# B293B_PSU.net
KiCad netlist of a schematic drawn in Altium Designer
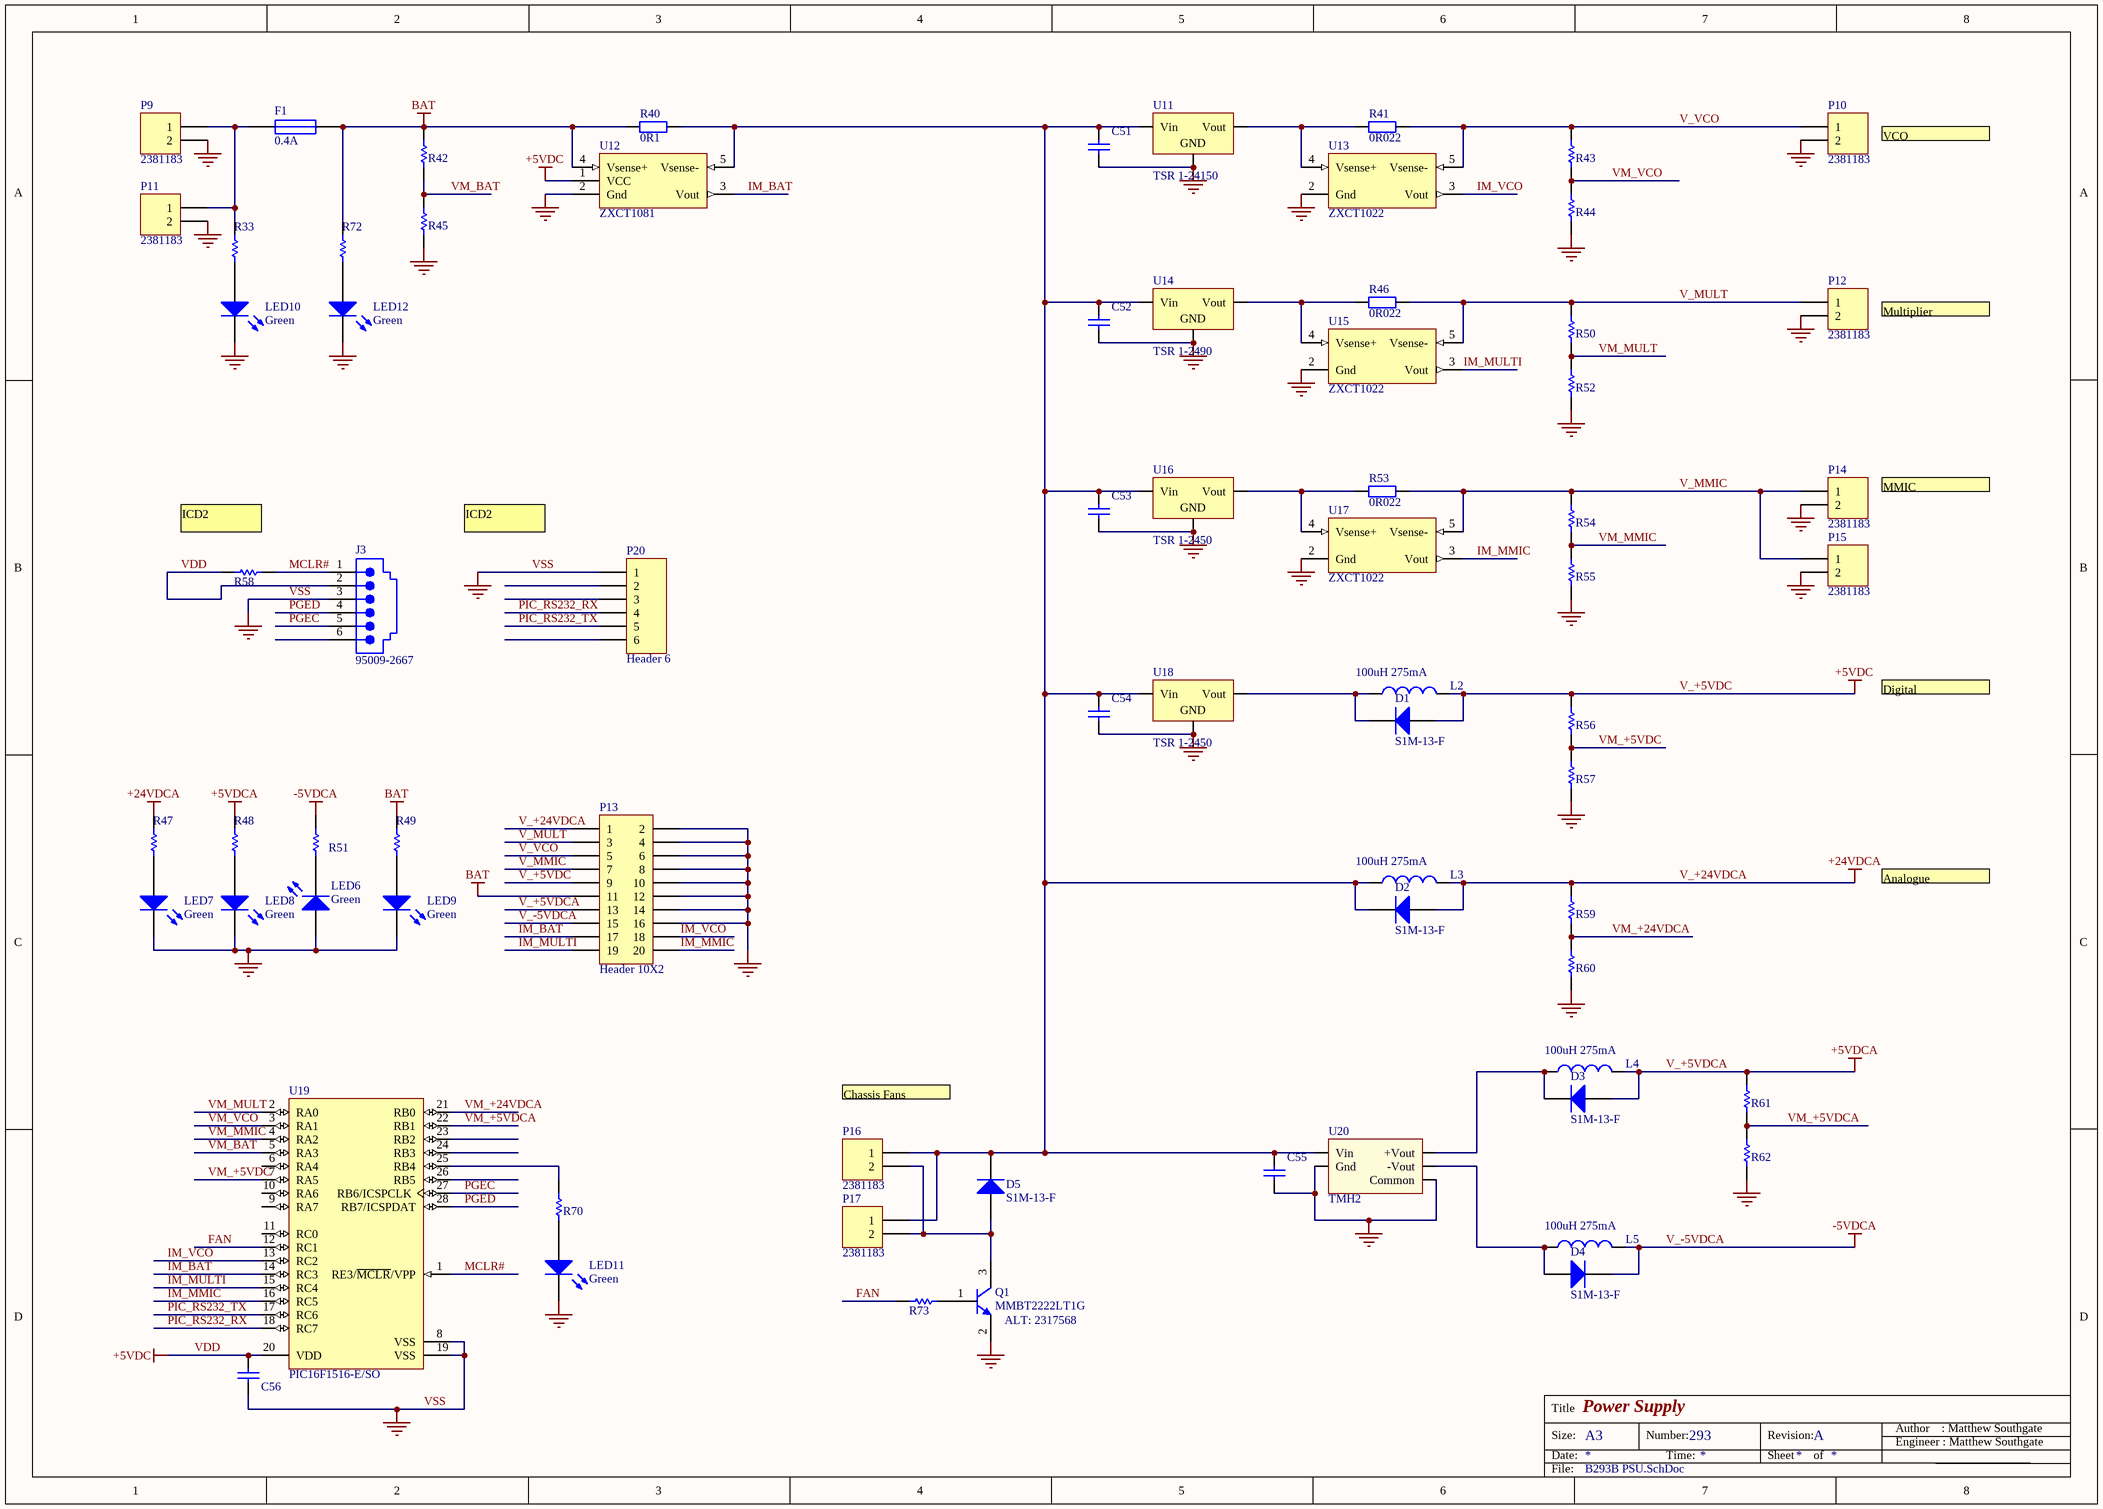
[diagram p0: B293B PSU.SchDoc]

(export (version "E")
  (design (tool "Eeschema 10.0.6"))
  (components
    (comp (ref "C51")
      (value "CAP 10uF 25V 0805(2012)")
      (footprint "CAPC0805(2012)145_N")
      (description "CAP 10uF 25V ±20% 0805 (2012 Metric) Thickness 1.45mm SMD")
      (fields (field (name "TOLERANCE") "±20%"))
      (libsource (lib "Altium Content Vault") (part "CAP"))
    )
    (comp (ref "C52")
      (value "CAP 10uF 25V 0805(2012)")
      (footprint "CAPC0805(2012)145_N")
      (description "CAP 10uF 25V ±20% 0805 (2012 Metric) Thickness 1.45mm SMD")
      (fields (field (name "TOLERANCE") "±20%"))
      (libsource (lib "Altium Content Vault") (part "CAP"))
    )
    (comp (ref "C53")
      (value "CAP 10uF 25V 0805(2012)")
      (footprint "CAPC0805(2012)145_N")
      (description "CAP 10uF 25V ±20% 0805 (2012 Metric) Thickness 1.45mm SMD")
      (fields (field (name "TOLERANCE") "±20%"))
      (libsource (lib "Altium Content Vault") (part "CAP"))
    )
    (comp (ref "C54")
      (value "CAP 10uF 25V 0805(2012)")
      (footprint "CAPC0805(2012)145_N")
      (description "CAP 10uF 25V ±20% 0805 (2012 Metric) Thickness 1.45mm SMD")
      (fields (field (name "TOLERANCE") "±20%"))
      (libsource (lib "Altium Content Vault") (part "CAP"))
    )
    (comp (ref "C55")
      (value "CAP 10uF 25V 0805(2012)")
      (footprint "CAPC0805(2012)145_N")
      (description "CAP 10uF 25V ±20% 0805 (2012 Metric) Thickness 1.45mm SMD")
      (fields (field (name "TOLERANCE") "±20%"))
      (libsource (lib "Altium Content Vault") (part "CAP"))
    )
    (comp (ref "C56")
      (value "CAP 100nF 50V 0805(2012)")
      (footprint "CAPC0805(2012)100_M")
      (description "CAP 100nF 50V ±20% 0805 (2012 Metric) Thickness 1mm SMD")
      (fields (field (name "TOLERANCE") "±20%"))
      (libsource (lib "Altium Content Vault") (part "CAP"))
    )
    (comp (ref "D1")
      (value "S1M-13-F")
      (footprint "DIOD-S1M-13-F-SMA-2_V")
      (fields (field (name "MANUFACTURER") "Diodes Inc"))
      (libsource (lib "Altium Content Vault") (part "DIOD-D-A1K2-2"))
    )
    (comp (ref "D2")
      (value "S1M-13-F")
      (footprint "DIOD-S1M-13-F-SMA-2_V")
      (fields (field (name "MANUFACTURER") "Diodes Inc"))
      (libsource (lib "Altium Content Vault") (part "DIOD-D-A1K2-2"))
    )
    (comp (ref "D3")
      (value "S1M-13-F")
      (footprint "DIOD-S1M-13-F-SMA-2_V")
      (fields (field (name "MANUFACTURER") "Diodes Inc"))
      (libsource (lib "Altium Content Vault") (part "DIOD-D-A1K2-2"))
    )
    (comp (ref "D4")
      (value "S1M-13-F")
      (footprint "DIOD-S1M-13-F-SMA-2_V")
      (fields (field (name "MANUFACTURER") "Diodes Inc"))
      (libsource (lib "Altium Content Vault") (part "DIOD-D-A1K2-2"))
    )
    (comp (ref "D5")
      (value "S1M-13-F")
      (footprint "DIOD-S1M-13-F-SMA-2_V")
      (fields (field (name "MANUFACTURER") "Diodes Inc"))
      (libsource (lib "Altium Content Vault") (part "DIOD-D-A1K2-2"))
    )
    (comp (ref "F1")
      (value "0.4A")
      (footprint "Matt PCB Library:RXEF040")
      (description "POLYSWITCH, RADIAL, 0.4A")
      (fields
        (field (name "MANUFACTURER PART NUMBER") "RXEF040")
        (field (name "MANUFACTURER") "TE CONNECTIVITY / RAYCHEM")
      )
      (libsource (lib "Matt SCH Library") (part "Fuse Poly 0.4A"))
    )
    (comp (ref "J3")
      (value "95009-2667")
      (footprint "95009-2667")
      (description "Right Angle, Standard Profile, Flush Mount PCB Jack")
      (fields (field (name "MANUFACTURER") "MOLEX") (field (name "PUBLISHER") "Altium Limited"))
      (libsource (lib "Matt SCH Library") (part "95009-2667"))
    )
    (comp (ref "L2")
      (value "100uH 275mA")
      (footprint "AXIAL-0.4")
      (description "Power Inductor")
      (fields
        (field (name "MANUFACTURER PART NUMBER") "MCAL0410A1-101KU")
        (field (name "MANUFACTURER") "MULTICOMP")
      )
      (libsource (lib "Matt SCH Library") (part "Inductor"))
    )
    (comp (ref "L3")
      (value "100uH 275mA")
      (footprint "AXIAL-0.4")
      (description "Power Inductor")
      (fields
        (field (name "MANUFACTURER PART NUMBER") "MCAL0410A1-101KU")
        (field (name "MANUFACTURER") "MULTICOMP")
      )
      (libsource (lib "Matt SCH Library") (part "Inductor"))
    )
    (comp (ref "L4")
      (value "100uH 275mA")
      (footprint "AXIAL-0.4")
      (description "Power Inductor")
      (fields
        (field (name "MANUFACTURER PART NUMBER") "MCAL0410A1-101KU")
        (field (name "MANUFACTURER") "MULTICOMP")
      )
      (libsource (lib "Matt SCH Library") (part "Inductor"))
    )
    (comp (ref "L5")
      (value "100uH 275mA")
      (footprint "AXIAL-0.4")
      (description "Power Inductor")
      (fields
        (field (name "MANUFACTURER PART NUMBER") "MCAL0410A1-101KU")
        (field (name "MANUFACTURER") "MULTICOMP")
      )
      (libsource (lib "Matt SCH Library") (part "Inductor"))
    )
    (comp (ref "LED6")
      (value "Green")
      (footprint "Matt PCB Library:1206 - LED")
      (description "LED, SMD, 1206, CLR LENS, GREEN")
      (fields
        (field (name "MANUFACTURER PART NUMBER") "KPC-3216SGC")
        (field (name "MANUFACTURER") "KINGBRIGHT")
      )
      (libsource (lib "Matt SCH Library") (part "LED 1206 GREEN"))
    )
    (comp (ref "LED7")
      (value "Green")
      (footprint "Matt PCB Library:1206 - LED")
      (description "LED, SMD, 1206, CLR LENS, GREEN")
      (fields
        (field (name "MANUFACTURER PART NUMBER") "KPC-3216SGC")
        (field (name "MANUFACTURER") "KINGBRIGHT")
      )
      (libsource (lib "Matt SCH Library") (part "LED 1206 GREEN"))
    )
    (comp (ref "LED8")
      (value "Green")
      (footprint "Matt PCB Library:1206 - LED")
      (description "LED, SMD, 1206, CLR LENS, GREEN")
      (fields
        (field (name "MANUFACTURER PART NUMBER") "KPC-3216SGC")
        (field (name "MANUFACTURER") "KINGBRIGHT")
      )
      (libsource (lib "Matt SCH Library") (part "LED 1206 GREEN"))
    )
    (comp (ref "LED9")
      (value "Green")
      (footprint "Matt PCB Library:1206 - LED")
      (description "LED, SMD, 1206, CLR LENS, GREEN")
      (fields
        (field (name "MANUFACTURER PART NUMBER") "KPC-3216SGC")
        (field (name "MANUFACTURER") "KINGBRIGHT")
      )
      (libsource (lib "Matt SCH Library") (part "LED 1206 GREEN"))
    )
    (comp (ref "LED10")
      (value "Green")
      (footprint "Matt PCB Library:1206 - LED")
      (description "LED, SMD, 1206, CLR LENS, GREEN")
      (fields
        (field (name "MANUFACTURER PART NUMBER") "KPC-3216SGC")
        (field (name "MANUFACTURER") "KINGBRIGHT")
      )
      (libsource (lib "Matt SCH Library") (part "LED 1206 GREEN"))
    )
    (comp (ref "LED11")
      (value "Green")
      (footprint "Matt PCB Library:1206 - LED")
      (description "LED, SMD, 1206, CLR LENS, GREEN")
      (fields
        (field (name "MANUFACTURER PART NUMBER") "KPC-3216SGC")
        (field (name "MANUFACTURER") "KINGBRIGHT")
      )
      (libsource (lib "Matt SCH Library") (part "LED 1206 GREEN"))
    )
    (comp (ref "LED12")
      (value "Green")
      (footprint "Matt PCB Library:1206 - LED")
      (description "LED, SMD, 1206, CLR LENS, GREEN")
      (fields
        (field (name "MANUFACTURER PART NUMBER") "KPC-3216SGC")
        (field (name "MANUFACTURER") "KINGBRIGHT")
      )
      (libsource (lib "Matt SCH Library") (part "LED 1206 GREEN"))
    )
    (comp (ref "P9")
      (value "MOLEX SL 2W VERT")
      (footprint "MOLEX SL 2W Vertical with latch")
      (description "MOLEX - 70543-0106 - CONNECTOR, HEADER, 2POS, 1ROW, 2.54MM")
      (fields
        (field (name "MANUFACTURER PART NUMBER") "70543-0106")
        (field (name "MANUFACTURER") "MOLEX")
        (field (name "SUPPLIER PART NUMBER 1") "2381183")
      )
      (libsource (lib "") (part "MOLEX SL 2W VERT_1"))
    )
    (comp (ref "P10")
      (value "MOLEX SL 2W VERT")
      (footprint "MOLEX SL 2W Vertical with latch")
      (description "MOLEX - 70543-0106 - CONNECTOR, HEADER, 2POS, 1ROW, 2.54MM")
      (fields
        (field (name "MANUFACTURER PART NUMBER") "70543-0106")
        (field (name "MANUFACTURER") "MOLEX")
        (field (name "SUPPLIER PART NUMBER 1") "2381183")
      )
      (libsource (lib "Matt SCH Library") (part "MOLEX SL 2W VERT"))
    )
    (comp (ref "P11")
      (value "MOLEX SL 2W VERT")
      (footprint "MOLEX SL 2W Vertical with latch")
      (description "MOLEX - 70543-0106 - CONNECTOR, HEADER, 2POS, 1ROW, 2.54MM")
      (fields
        (field (name "MANUFACTURER PART NUMBER") "70543-0106")
        (field (name "MANUFACTURER") "MOLEX")
        (field (name "SUPPLIER PART NUMBER 1") "2381183")
      )
      (libsource (lib "") (part "MOLEX SL 2W VERT_1"))
    )
    (comp (ref "P12")
      (value "MOLEX SL 2W VERT")
      (footprint "MOLEX SL 2W Vertical with latch")
      (description "MOLEX - 70543-0106 - CONNECTOR, HEADER, 2POS, 1ROW, 2.54MM")
      (fields
        (field (name "MANUFACTURER PART NUMBER") "70543-0106")
        (field (name "MANUFACTURER") "MOLEX")
        (field (name "SUPPLIER PART NUMBER 1") "2381183")
      )
      (libsource (lib "Matt SCH Library") (part "MOLEX SL 2W VERT"))
    )
    (comp (ref "P13")
      (value "Header 10X2")
      (footprint "HDR2X10")
      (description "Header, 10-Pin, Dual row")
      (fields (field (name "PUBLISHER") "Altium Limited"))
      (libsource (lib "Miscellaneous Connectors") (part "Header 10X2"))
    )
    (comp (ref "P14")
      (value "MOLEX SL 2W VERT")
      (footprint "MOLEX SL 2W Vertical with latch")
      (description "MOLEX - 70543-0106 - CONNECTOR, HEADER, 2POS, 1ROW, 2.54MM")
      (fields
        (field (name "MANUFACTURER PART NUMBER") "70543-0106")
        (field (name "MANUFACTURER") "MOLEX")
        (field (name "SUPPLIER PART NUMBER 1") "2381183")
      )
      (libsource (lib "Matt SCH Library") (part "MOLEX SL 2W VERT"))
    )
    (comp (ref "P15")
      (value "MOLEX SL 2W VERT")
      (footprint "MOLEX SL 2W Vertical with latch")
      (description "MOLEX - 70543-0106 - CONNECTOR, HEADER, 2POS, 1ROW, 2.54MM")
      (fields
        (field (name "MANUFACTURER PART NUMBER") "70543-0106")
        (field (name "MANUFACTURER") "MOLEX")
        (field (name "SUPPLIER PART NUMBER 1") "2381183")
      )
      (libsource (lib "Matt SCH Library") (part "MOLEX SL 2W VERT"))
    )
    (comp (ref "P16")
      (value "MOLEX SL 2W VERT")
      (footprint "MOLEX SL 2W Vertical with latch")
      (description "MOLEX - 70543-0106 - CONNECTOR, HEADER, 2POS, 1ROW, 2.54MM")
      (fields
        (field (name "MANUFACTURER PART NUMBER") "70543-0106")
        (field (name "MANUFACTURER") "MOLEX")
        (field (name "SUPPLIER PART NUMBER 1") "2381183")
      )
      (libsource (lib "") (part "MOLEX SL 2W VERT_1"))
    )
    (comp (ref "P17")
      (value "MOLEX SL 2W VERT")
      (footprint "MOLEX SL 2W Vertical with latch")
      (description "MOLEX - 70543-0106 - CONNECTOR, HEADER, 2POS, 1ROW, 2.54MM")
      (fields
        (field (name "MANUFACTURER PART NUMBER") "70543-0106")
        (field (name "MANUFACTURER") "MOLEX")
        (field (name "SUPPLIER PART NUMBER 1") "2381183")
      )
      (libsource (lib "") (part "MOLEX SL 2W VERT_1"))
    )
    (comp (ref "P20")
      (value "Header 6")
      (footprint "HDR1X6")
      (description "Header, 6-Pin")
      (fields (field (name "PUBLISHER") "Altium Limited"))
      (libsource (lib "Miscellaneous Connectors") (part "Header 6"))
    )
    (comp (ref "Q1")
      (value "MMBT2222LT1G")
      (footprint "ONSC-SOT-23-3-318-08_M")
      (description "General Purpose Transistor, NPN, 0.6 A IC Continuous, 3-Pin SOT23, RoHS, Tape and Reel")
      (fields (field (name "MANUFACTURER") "ON Semiconductor"))
      (libsource (lib "Altium Content Vault") (part "ONSC-NPN_B1E2C3-3"))
    )
    (comp (ref "R33")
      (value "10K 5% 0805(2012)")
      (footprint "RESC0805(2012)_L")
      (description "10K 0.125W 5% 0805 (2012 Metric)  SMD")
      (fields (field (name "TOLERANCE") "5 %") (field (name "POWER") "0.125 W"))
      (libsource (lib "Altium Content Vault") (part "RES"))
    )
    (comp (ref "R40")
      (value "0R1")
      (footprint "1206")
      (description "RESISTOR, THICK, 0.1OHM, 0.25W, 1%, 1206")
      (fields (field (name "MANUFACTURER PART NUMBER") "CRL1206-FW-R100ELF"))
      (libsource (lib "Matt SCH Library") (part "RES_0R1"))
    )
    (comp (ref "R41")
      (value "0R022")
      (footprint "1206")
      (description "RESISTOR, CURRENT SENSE, 0R022, 0.5W, 1%")
      (fields
        (field (name "MANUFACTURER") "MULTICOMP")
        (field (name "MANUFACTURER PART NUMBER") "MCCSM06FTDUR022")
      )
      (libsource (lib "Matt SCH Library") (part "RES_0R022"))
    )
    (comp (ref "R42")
      (value "1K 5% 0805(2012)")
      (footprint "RESC0805(2012)_N")
      (description "1K 0.125W 5% 0805 (2012 Metric)  SMD")
      (fields (field (name "POWER") "0.125 W") (field (name "TOLERANCE") "5 %"))
      (libsource (lib "Altium Content Vault") (part "RES"))
    )
    (comp (ref "R43")
      (value "1K 5% 0805(2012)")
      (footprint "RESC0805(2012)_N")
      (description "1K 0.125W 5% 0805 (2012 Metric)  SMD")
      (fields (field (name "POWER") "0.125 W") (field (name "TOLERANCE") "5 %"))
      (libsource (lib "Altium Content Vault") (part "RES"))
    )
    (comp (ref "R44")
      (value "390R 5% 0805(2012)")
      (footprint "RESC0805(2012)_N")
      (description "390R 0.125W 5% 0805 (2012 Metric)  SMD")
      (fields (field (name "TOLERANCE") "5 %") (field (name "POWER") "0.125 W"))
      (libsource (lib "Altium Content Vault") (part "RES"))
    )
    (comp (ref "R45")
      (value "220R 5% 0805(2012)")
      (footprint "RESC0805(2012)_L")
      (description "220R 0.125W 5% 0805 (2012 Metric)  SMD")
      (fields (field (name "TOLERANCE") "5 %") (field (name "POWER") "0.125 W"))
      (libsource (lib "Altium Content Vault") (part "RES"))
    )
    (comp (ref "R46")
      (value "0R022")
      (footprint "1206")
      (description "RESISTOR, CURRENT SENSE, 0R022, 0.5W, 1%")
      (fields
        (field (name "MANUFACTURER") "MULTICOMP")
        (field (name "MANUFACTURER PART NUMBER") "MCCSM06FTDUR022")
      )
      (libsource (lib "Matt SCH Library") (part "RES_0R022"))
    )
    (comp (ref "R47")
      (value "6K8 5% 0805(2012)")
      (footprint "RESC0805(2012)_L")
      (description "6K8 0.125W 5% 0805 (2012 Metric)  SMD")
      (fields (field (name "POWER") "0.125 W") (field (name "TOLERANCE") "5 %"))
      (libsource (lib "Altium Content Vault") (part "RES"))
    )
    (comp (ref "R48")
      (value "1K 5% 0805(2012)")
      (footprint "RESC0805(2012)_N")
      (description "1K 0.125W 5% 0805 (2012 Metric)  SMD")
      (fields (field (name "POWER") "0.125 W") (field (name "TOLERANCE") "5 %"))
      (libsource (lib "Altium Content Vault") (part "RES"))
    )
    (comp (ref "R49")
      (value "10K 5% 0805(2012)")
      (footprint "RESC0805(2012)_L")
      (description "10K 0.125W 5% 0805 (2012 Metric)  SMD")
      (fields (field (name "TOLERANCE") "5 %") (field (name "POWER") "0.125 W"))
      (libsource (lib "Altium Content Vault") (part "RES"))
    )
    (comp (ref "R50")
      (value "1K 5% 0805(2012)")
      (footprint "RESC0805(2012)_N")
      (description "1K 0.125W 5% 0805 (2012 Metric)  SMD")
      (fields (field (name "POWER") "0.125 W") (field (name "TOLERANCE") "5 %"))
      (libsource (lib "Altium Content Vault") (part "RES"))
    )
    (comp (ref "R51")
      (value "1K 5% 0805(2012)")
      (footprint "RESC0805(2012)_N")
      (description "1K 0.125W 5% 0805 (2012 Metric)  SMD")
      (fields (field (name "POWER") "0.125 W") (field (name "TOLERANCE") "5 %"))
      (libsource (lib "Altium Content Vault") (part "RES"))
    )
    (comp (ref "R52")
      (value "1K 5% 0805(2012)")
      (footprint "RESC0805(2012)_N")
      (description "1K 0.125W 5% 0805 (2012 Metric)  SMD")
      (fields (field (name "POWER") "0.125 W") (field (name "TOLERANCE") "5 %"))
      (libsource (lib "Altium Content Vault") (part "RES"))
    )
    (comp (ref "R53")
      (value "0R022")
      (footprint "1206")
      (description "RESISTOR, CURRENT SENSE, 0R022, 0.5W, 1%")
      (fields
        (field (name "MANUFACTURER") "MULTICOMP")
        (field (name "MANUFACTURER PART NUMBER") "MCCSM06FTDUR022")
      )
      (libsource (lib "Matt SCH Library") (part "RES_0R022"))
    )
    (comp (ref "R54")
      (value "1K 5% 0805(2012)")
      (footprint "RESC0805(2012)_N")
      (description "1K 0.125W 5% 0805 (2012 Metric)  SMD")
      (fields (field (name "POWER") "0.125 W") (field (name "TOLERANCE") "5 %"))
      (libsource (lib "Altium Content Vault") (part "RES"))
    )
    (comp (ref "R55")
      (value "10K 5% 0805(2012)")
      (footprint "RESC0805(2012)_L")
      (description "10K 0.125W 5% 0805 (2012 Metric)  SMD")
      (fields (field (name "POWER") "0.125 W") (field (name "TOLERANCE") "5 %"))
      (libsource (lib "Altium Content Vault") (part "RES"))
    )
    (comp (ref "R56")
      (value "1K 5% 0805(2012)")
      (footprint "RESC0805(2012)_N")
      (description "1K 0.125W 5% 0805 (2012 Metric)  SMD")
      (fields (field (name "POWER") "0.125 W") (field (name "TOLERANCE") "5 %"))
      (libsource (lib "Altium Content Vault") (part "RES"))
    )
    (comp (ref "R57")
      (value "10K 5% 0805(2012)")
      (footprint "RESC0805(2012)_L")
      (description "10K 0.125W 5% 0805 (2012 Metric)  SMD")
      (fields (field (name "POWER") "0.125 W") (field (name "TOLERANCE") "5 %"))
      (libsource (lib "Altium Content Vault") (part "RES"))
    )
    (comp (ref "R58")
      (value "10K 5% 0805(2012)")
      (footprint "RESC0805(2012)_L")
      (description "10K 0.125W 5% 0805 (2012 Metric)  SMD")
      (fields (field (name "POWER") "0.125 W") (field (name "TOLERANCE") "5 %"))
      (libsource (lib "Altium Content Vault") (part "RES"))
    )
    (comp (ref "R59")
      (value "1K 5% 0805(2012)")
      (footprint "RESC0805(2012)_N")
      (description "1K 0.125W 5% 0805 (2012 Metric)  SMD")
      (fields (field (name "POWER") "0.125 W") (field (name "TOLERANCE") "5 %"))
      (libsource (lib "Altium Content Vault") (part "RES"))
    )
    (comp (ref "R60")
      (value "220R 5% 0805(2012)")
      (footprint "RESC0805(2012)_L")
      (description "220R 0.125W 5% 0805 (2012 Metric)  SMD")
      (fields (field (name "TOLERANCE") "5 %") (field (name "POWER") "0.125 W"))
      (libsource (lib "Altium Content Vault") (part "RES"))
    )
    (comp (ref "R61")
      (value "1K 5% 0805(2012)")
      (footprint "RESC0805(2012)_N")
      (description "1K 0.125W 5% 0805 (2012 Metric)  SMD")
      (fields (field (name "POWER") "0.125 W") (field (name "TOLERANCE") "5 %"))
      (libsource (lib "Altium Content Vault") (part "RES"))
    )
    (comp (ref "R62")
      (value "10K 5% 0805(2012)")
      (footprint "RESC0805(2012)_L")
      (description "10K 0.125W 5% 0805 (2012 Metric)  SMD")
      (fields (field (name "POWER") "0.125 W") (field (name "TOLERANCE") "5 %"))
      (libsource (lib "Altium Content Vault") (part "RES"))
    )
    (comp (ref "R70")
      (value "1K 5% 0805(2012)")
      (footprint "RESC0805(2012)_N")
      (description "1K 0.125W 5% 0805 (2012 Metric)  SMD")
      (fields (field (name "POWER") "0.125 W") (field (name "TOLERANCE") "5 %"))
      (libsource (lib "Altium Content Vault") (part "RES"))
    )
    (comp (ref "R72")
      (value "10K 5% 0805(2012)")
      (footprint "RESC0805(2012)_L")
      (description "10K 0.125W 5% 0805 (2012 Metric)  SMD")
      (fields (field (name "TOLERANCE") "5 %") (field (name "POWER") "0.125 W"))
      (libsource (lib "Altium Content Vault") (part "CMP-1013-00098-1"))
    )
    (comp (ref "R73")
      (value "270R 5% 0805(2012)")
      (footprint "RESC0805(2012)_N")
      (description "270R 0.125W 5% 0805 (2012 Metric)  SMD")
      (fields (field (name "POWER") "0.125 W") (field (name "TOLERANCE") "5 %"))
      (libsource (lib "Altium Content Vault") (part "RES"))
    )
    (comp (ref "U11")
      (value "TSR 1-24150")
      (footprint "Matt PCB Library:TSR-1 Series")
      (description "CONVERTER, DC TO DC, 24V TO 15V, 15W")
      (fields (field (name "MANUFACTURER") "TRACOPOWER"))
      (libsource (lib "Matt SCH Library") (part "TSR-1 Series DC-DC 15V"))
    )
    (comp (ref "U12")
      (value "ZXCT1081")
      (footprint "SOT23-5")
      (description "CURRENT MONITOR, PRECISION, 40V")
      (fields
        (field (name "MANCUFACTURER PART NUMBER") "ZXCT1081E5TA")
        (field (name "MANUFACTURER") "DIODES INC.")
      )
      (libsource (lib "Matt SCH Library") (part "ZXCT1081"))
    )
    (comp (ref "U13")
      (value "ZXCT1022")
      (footprint "SOT23-5")
      (fields
        (field (name "MANUFACTURER") "DIODES INC.")
        (field (name "MANUFACTURER PART NUMBER") "ZXCT1022E5TA")
      )
      (libsource (lib "Matt SCH Library") (part "ZXCT1022"))
    )
    (comp (ref "U14")
      (value "TSR 1-2490")
      (footprint "Matt PCB Library:TSR-1 Series")
      (description "DC/DC CONVERTER, 9V, 1A,")
      (fields (field (name "MANUFACTURER") "TRACOPOWER"))
      (libsource (lib "Matt SCH Library") (part "TSR-1 Series DC-DC 9V"))
    )
    (comp (ref "U15")
      (value "ZXCT1022")
      (footprint "SOT23-5")
      (fields
        (field (name "MANUFACTURER") "DIODES INC.")
        (field (name "MANUFACTURER PART NUMBER") "ZXCT1022E5TA")
      )
      (libsource (lib "Matt SCH Library") (part "ZXCT1022"))
    )
    (comp (ref "U16")
      (value "TSR 1-2450")
      (footprint "Matt PCB Library:TSR-1 Series")
      (description "CONVERTER, DC/DC, 5V, 1A, SIP")
      (fields (field (name "MANUFACTURER") "TRACOPOWER"))
      (libsource (lib "Matt SCH Library") (part "TSR-1 Series DC-DC 5V"))
    )
    (comp (ref "U17")
      (value "ZXCT1022")
      (footprint "SOT23-5")
      (fields
        (field (name "MANUFACTURER") "DIODES INC.")
        (field (name "MANUFACTURER PART NUMBER") "ZXCT1022E5TA")
      )
      (libsource (lib "Matt SCH Library") (part "ZXCT1022"))
    )
    (comp (ref "U18")
      (value "TSR 1-2450")
      (footprint "Matt PCB Library:TSR-1 Series")
      (description "CONVERTER, DC/DC, 5V, 1A, SIP")
      (fields (field (name "MANUFACTURER") "TRACOPOWER"))
      (libsource (lib "Matt SCH Library") (part "TSR-1 Series DC-DC 5V"))
    )
    (comp (ref "U19")
      (value "PIC16F1516-E/SO")
      (footprint "MCHP-SOIC-SO28_N")
      (fields (field (name "MANUFACTURER") "Microchip"))
      (libsource (lib "Altium Content Vault") (part "CMP-0115-02502-1"))
    )
    (comp (ref "U20")
      (value "TMH2")
      (footprint "Matt PCB Library:TMH2 Dual output")
      (description "Isolated output")
      (fields
        (field (name "MANUFACTURER") "TRACOPOWER")
        (field (name "MANUFACTURER PART NUMBER") "TMH 2405D")
      )
      (libsource (lib "Matt SCH Library") (part "TMH2 Series Dual DC-DC"))
    )
  )
  (nets
    (net (code "1") (name "+5VDC") (class "Default")
      (node (ref "C56") (pin "1") (pinfunction "1_1") (pintype "passive"))
      (node (ref "D1") (pin "1") (pinfunction "A_1") (pintype "passive"))
      (node (ref "J3") (pin "2") (pinfunction "2_2") (pintype "passive"))
      (node (ref "L2") (pin "2") (pinfunction "2_2") (pintype "passive"))
      (node (ref "P13") (pin "9") (pinfunction "9_9") (pintype "passive"))
      (node (ref "R56") (pin "2") (pinfunction "2_2") (pintype "passive"))
      (node (ref "R58") (pin "1") (pinfunction "1_1") (pintype "passive"))
      (node (ref "U12") (pin "1") (pinfunction "VCC_1") (pintype "power_in"))
      (node (ref "U19") (pin "20") (pinfunction "VDD_20") (pintype "power_in"))
    )
    (net (code "2") (name "+5VDCA") (class "Default")
      (node (ref "D3") (pin "1") (pinfunction "A_1") (pintype "passive"))
      (node (ref "L4") (pin "2") (pinfunction "2_2") (pintype "passive"))
      (node (ref "P13") (pin "13") (pinfunction "13_13") (pintype "passive"))
      (node (ref "R48") (pin "2") (pinfunction "2_2") (pintype "passive"))
      (node (ref "R61") (pin "2") (pinfunction "2_2") (pintype "passive"))
    )
    (net (code "3") (name "+24VDCA") (class "Default")
      (node (ref "D2") (pin "1") (pinfunction "A_1") (pintype "passive"))
      (node (ref "L3") (pin "2") (pinfunction "2_2") (pintype "passive"))
      (node (ref "P13") (pin "1") (pinfunction "1_1") (pintype "passive"))
      (node (ref "R47") (pin "2") (pinfunction "2_2") (pintype "passive"))
      (node (ref "R59") (pin "2") (pinfunction "2_2") (pintype "passive"))
    )
    (net (code "4") (name "-5VDCA") (class "Default")
      (node (ref "D4") (pin "2") (pinfunction "K_2") (pintype "passive"))
      (node (ref "L5") (pin "2") (pinfunction "2_2") (pintype "passive"))
      (node (ref "P13") (pin "15") (pinfunction "15_15") (pintype "passive"))
      (node (ref "R51") (pin "1") (pinfunction "1_1") (pintype "passive"))
    )
    (net (code "5") (name "/FAN") (class "Default")
      (node (ref "R73") (pin "1") (pinfunction "1_1") (pintype "passive"))
      (node (ref "U19") (pin "12") (pinfunction "RC1_12") (pintype "bidirectional"))
    )
    (net (code "6") (name "/IM_BAT") (class "Default")
      (node (ref "P13") (pin "17") (pinfunction "17_17") (pintype "passive"))
      (node (ref "U12") (pin "3") (pinfunction "Vout_3") (pintype "output"))
      (node (ref "U19") (pin "14") (pinfunction "RC3_14") (pintype "bidirectional"))
    )
    (net (code "7") (name "/IM_MMIC") (class "Default")
      (node (ref "P13") (pin "20") (pinfunction "20_20") (pintype "passive"))
      (node (ref "U17") (pin "3") (pinfunction "Vout_3") (pintype "output"))
      (node (ref "U19") (pin "16") (pinfunction "RC5_16") (pintype "bidirectional"))
    )
    (net (code "8") (name "/IM_MULTI") (class "Default")
      (node (ref "P13") (pin "19") (pinfunction "19_19") (pintype "passive"))
      (node (ref "U15") (pin "3") (pinfunction "Vout_3") (pintype "output"))
      (node (ref "U19") (pin "15") (pinfunction "RC4_15") (pintype "bidirectional"))
    )
    (net (code "9") (name "/IM_VCO") (class "Default")
      (node (ref "P13") (pin "18") (pinfunction "18_18") (pintype "passive"))
      (node (ref "U13") (pin "3") (pinfunction "Vout_3") (pintype "output"))
      (node (ref "U19") (pin "13") (pinfunction "RC2_13") (pintype "bidirectional"))
    )
    (net (code "10") (name "/MCLR#") (class "Default")
      (node (ref "J3") (pin "1") (pinfunction "1_1") (pintype "passive"))
      (node (ref "R58") (pin "2") (pinfunction "2_2") (pintype "passive"))
      (node (ref "U19") (pin "1") (pinfunction "RE3/~{MCLR}/VPP_1") (pintype "input"))
    )
    (net (code "11") (name "/PGEC") (class "Default")
      (node (ref "J3") (pin "5") (pinfunction "5_5") (pintype "passive"))
      (node (ref "U19") (pin "27") (pinfunction "RB6/ICSPCLK_27") (pintype "bidirectional"))
    )
    (net (code "12") (name "/PGED") (class "Default")
      (node (ref "J3") (pin "4") (pinfunction "4_4") (pintype "passive"))
      (node (ref "U19") (pin "28") (pinfunction "RB7/ICSPDAT_28") (pintype "bidirectional"))
    )
    (net (code "13") (name "/PIC_RS232_RX") (class "Default")
      (node (ref "P20") (pin "4") (pinfunction "4_4") (pintype "passive"))
      (node (ref "U19") (pin "18") (pinfunction "RC7_18") (pintype "bidirectional"))
    )
    (net (code "14") (name "/PIC_RS232_TX") (class "Default")
      (node (ref "P20") (pin "5") (pinfunction "5_5") (pintype "passive"))
      (node (ref "U19") (pin "17") (pinfunction "RC6_17") (pintype "bidirectional"))
    )
    (net (code "15") (name "/VM_+5VDC") (class "Default")
      (node (ref "R56") (pin "1") (pinfunction "1_1") (pintype "passive"))
      (node (ref "R57") (pin "2") (pinfunction "2_2") (pintype "passive"))
      (node (ref "U19") (pin "7") (pinfunction "RA5_7") (pintype "bidirectional"))
    )
    (net (code "16") (name "/VM_+5VDCA") (class "Default")
      (node (ref "R61") (pin "1") (pinfunction "1_1") (pintype "passive"))
      (node (ref "R62") (pin "2") (pinfunction "2_2") (pintype "passive"))
      (node (ref "U19") (pin "22") (pinfunction "RB1_22") (pintype "bidirectional"))
    )
    (net (code "17") (name "/VM_+24VDCA") (class "Default")
      (node (ref "R59") (pin "1") (pinfunction "1_1") (pintype "passive"))
      (node (ref "R60") (pin "2") (pinfunction "2_2") (pintype "passive"))
      (node (ref "U19") (pin "21") (pinfunction "RB0_21") (pintype "bidirectional"))
    )
    (net (code "18") (name "/VM_BAT") (class "Default")
      (node (ref "R42") (pin "1") (pinfunction "1_1") (pintype "passive"))
      (node (ref "R45") (pin "2") (pinfunction "2_2") (pintype "passive"))
      (node (ref "U19") (pin "5") (pinfunction "RA3_5") (pintype "bidirectional"))
    )
    (net (code "19") (name "/VM_MMIC") (class "Default")
      (node (ref "R54") (pin "1") (pinfunction "1_1") (pintype "passive"))
      (node (ref "R55") (pin "2") (pinfunction "2_2") (pintype "passive"))
      (node (ref "U19") (pin "4") (pinfunction "RA2_4") (pintype "bidirectional"))
    )
    (net (code "20") (name "/VM_MULT") (class "Default")
      (node (ref "R50") (pin "1") (pinfunction "1_1") (pintype "passive"))
      (node (ref "R52") (pin "2") (pinfunction "2_2") (pintype "passive"))
      (node (ref "U19") (pin "2") (pinfunction "RA0_2") (pintype "bidirectional"))
    )
    (net (code "21") (name "/VM_VCO") (class "Default")
      (node (ref "R43") (pin "1") (pinfunction "1_1") (pintype "passive"))
      (node (ref "R44") (pin "2") (pinfunction "2_2") (pintype "passive"))
      (node (ref "U19") (pin "3") (pinfunction "RA1_3") (pintype "bidirectional"))
    )
    (net (code "22") (name "/V_MMIC") (class "Default")
      (node (ref "P13") (pin "7") (pinfunction "7_7") (pintype "passive"))
      (node (ref "P14") (pin "1") (pinfunction "1_1") (pintype "passive"))
      (node (ref "P15") (pin "1") (pinfunction "1_1") (pintype "passive"))
      (node (ref "R53") (pin "2") (pinfunction "2_2") (pintype "passive"))
      (node (ref "R54") (pin "2") (pinfunction "2_2") (pintype "passive"))
      (node (ref "U17") (pin "5") (pinfunction "Vsense-_5") (pintype "input"))
    )
    (net (code "23") (name "/V_MULT") (class "Default")
      (node (ref "P12") (pin "1") (pinfunction "1_1") (pintype "passive"))
      (node (ref "P13") (pin "3") (pinfunction "3_3") (pintype "passive"))
      (node (ref "R46") (pin "2") (pinfunction "2_2") (pintype "passive"))
      (node (ref "R50") (pin "2") (pinfunction "2_2") (pintype "passive"))
      (node (ref "U15") (pin "5") (pinfunction "Vsense-_5") (pintype "input"))
    )
    (net (code "24") (name "/V_VCO") (class "Default")
      (node (ref "P10") (pin "1") (pinfunction "1_1") (pintype "passive"))
      (node (ref "P13") (pin "5") (pinfunction "5_5") (pintype "passive"))
      (node (ref "R41") (pin "2") (pinfunction "2_2") (pintype "passive"))
      (node (ref "R43") (pin "2") (pinfunction "2_2") (pintype "passive"))
      (node (ref "U13") (pin "5") (pinfunction "Vsense-_5") (pintype "input"))
    )
    (net (code "25") (name "BAT") (class "Default")
      (node (ref "F1") (pin "2") (pintype "power_in"))
      (node (ref "P13") (pin "11") (pinfunction "11_11") (pintype "passive"))
      (node (ref "R40") (pin "2") (pinfunction "2_2") (pintype "passive"))
      (node (ref "R42") (pin "2") (pinfunction "2_2") (pintype "passive"))
      (node (ref "R49") (pin "2") (pinfunction "2_2") (pintype "passive"))
      (node (ref "R72") (pin "2") (pinfunction "2_2") (pintype "passive"))
      (node (ref "U12") (pin "4") (pinfunction "Vsense+_4") (pintype "input"))
    )
    (net (code "26") (name "GND") (class "Default")
      (node (ref "C51") (pin "1") (pinfunction "1_1") (pintype "passive"))
      (node (ref "C52") (pin "1") (pinfunction "1_1") (pintype "passive"))
      (node (ref "C53") (pin "1") (pinfunction "1_1") (pintype "passive"))
      (node (ref "C54") (pin "1") (pinfunction "1_1") (pintype "passive"))
      (node (ref "C55") (pin "1") (pinfunction "1_1") (pintype "passive"))
      (node (ref "C56") (pin "2") (pinfunction "2_2") (pintype "passive"))
      (node (ref "J3") (pin "3") (pinfunction "3_3") (pintype "passive"))
      (node (ref "LED10") (pin "K") (pinfunction "K_K") (pintype "passive"))
      (node (ref "LED11") (pin "K") (pinfunction "K_K") (pintype "passive"))
      (node (ref "LED12") (pin "K") (pinfunction "K_K") (pintype "passive"))
      (node (ref "LED6") (pin "A") (pinfunction "A_A") (pintype "passive"))
      (node (ref "LED7") (pin "K") (pinfunction "K_K") (pintype "passive"))
      (node (ref "LED8") (pin "K") (pinfunction "K_K") (pintype "passive"))
      (node (ref "LED9") (pin "K") (pinfunction "K_K") (pintype "passive"))
      (node (ref "P10") (pin "2") (pinfunction "2_2") (pintype "passive"))
      (node (ref "P11") (pin "2") (pinfunction "2_2") (pintype "passive"))
      (node (ref "P12") (pin "2") (pinfunction "2_2") (pintype "passive"))
      (node (ref "P13") (pin "10") (pinfunction "10_10") (pintype "passive"))
      (node (ref "P13") (pin "12") (pinfunction "12_12") (pintype "passive"))
      (node (ref "P13") (pin "14") (pinfunction "14_14") (pintype "passive"))
      (node (ref "P13") (pin "16") (pinfunction "16_16") (pintype "passive"))
      (node (ref "P13") (pin "2") (pinfunction "2_2") (pintype "passive"))
      (node (ref "P13") (pin "4") (pinfunction "4_4") (pintype "passive"))
      (node (ref "P13") (pin "6") (pinfunction "6_6") (pintype "passive"))
      (node (ref "P13") (pin "8") (pinfunction "8_8") (pintype "passive"))
      (node (ref "P14") (pin "2") (pinfunction "2_2") (pintype "passive"))
      (node (ref "P15") (pin "2") (pinfunction "2_2") (pintype "passive"))
      (node (ref "P20") (pin "1") (pinfunction "1_1") (pintype "passive"))
      (node (ref "P9") (pin "2") (pinfunction "2_2") (pintype "passive"))
      (node (ref "Q1") (pin "2") (pinfunction "E_2") (pintype "passive"))
      (node (ref "R44") (pin "1") (pinfunction "1_1") (pintype "passive"))
      (node (ref "R45") (pin "1") (pinfunction "1_1") (pintype "passive"))
      (node (ref "R52") (pin "1") (pinfunction "1_1") (pintype "passive"))
      (node (ref "R55") (pin "1") (pinfunction "1_1") (pintype "passive"))
      (node (ref "R57") (pin "1") (pinfunction "1_1") (pintype "passive"))
      (node (ref "R60") (pin "1") (pinfunction "1_1") (pintype "passive"))
      (node (ref "R62") (pin "1") (pinfunction "1_1") (pintype "passive"))
      (node (ref "U11") (pin "2") (pinfunction "GND_2") (pintype "passive"))
      (node (ref "U12") (pin "2") (pinfunction "Gnd_2") (pintype "power_in"))
      (node (ref "U13") (pin "2") (pinfunction "Gnd_2") (pintype "power_in"))
      (node (ref "U14") (pin "2") (pinfunction "GND_2") (pintype "passive"))
      (node (ref "U15") (pin "2") (pinfunction "Gnd_2") (pintype "power_in"))
      (node (ref "U16") (pin "2") (pinfunction "GND_2") (pintype "passive"))
      (node (ref "U17") (pin "2") (pinfunction "Gnd_2") (pintype "power_in"))
      (node (ref "U18") (pin "2") (pinfunction "GND_2") (pintype "passive"))
      (node (ref "U19") (pin "19") (pinfunction "VSS_19") (pintype "power_in"))
      (node (ref "U19") (pin "8") (pinfunction "VSS_8") (pintype "power_in"))
      (node (ref "U20") (pin "2") (pinfunction "Gnd_2") (pintype "passive"))
      (node (ref "U20") (pin "5") (pinfunction "Common_5") (pintype "passive"))
    )
    (net (code "27") (name "Net-(D1-K)") (class "Default")
      (node (ref "D1") (pin "2") (pinfunction "K_2") (pintype "passive"))
      (node (ref "L2") (pin "1") (pinfunction "1_1") (pintype "passive"))
      (node (ref "U18") (pin "3") (pinfunction "Vout_3") (pintype "passive"))
    )
    (net (code "28") (name "Net-(D2-K)") (class "Default")
      (node (ref "C51") (pin "2") (pinfunction "2_2") (pintype "passive"))
      (node (ref "C52") (pin "2") (pinfunction "2_2") (pintype "passive"))
      (node (ref "C53") (pin "2") (pinfunction "2_2") (pintype "passive"))
      (node (ref "C54") (pin "2") (pinfunction "2_2") (pintype "passive"))
      (node (ref "C55") (pin "2") (pinfunction "2_2") (pintype "passive"))
      (node (ref "D2") (pin "2") (pinfunction "K_2") (pintype "passive"))
      (node (ref "D5") (pin "2") (pinfunction "K_2") (pintype "passive"))
      (node (ref "L3") (pin "1") (pinfunction "1_1") (pintype "passive"))
      (node (ref "P16") (pin "1") (pinfunction "1_1") (pintype "passive"))
      (node (ref "P17") (pin "1") (pinfunction "1_1") (pintype "passive"))
      (node (ref "R40") (pin "1") (pinfunction "1_1") (pintype "passive"))
      (node (ref "U11") (pin "1") (pinfunction "Vin_1") (pintype "passive"))
      (node (ref "U12") (pin "5") (pinfunction "Vsense-_5") (pintype "input"))
      (node (ref "U14") (pin "1") (pinfunction "Vin_1") (pintype "passive"))
      (node (ref "U16") (pin "1") (pinfunction "Vin_1") (pintype "passive"))
      (node (ref "U18") (pin "1") (pinfunction "Vin_1") (pintype "passive"))
      (node (ref "U20") (pin "1") (pinfunction "Vin_1") (pintype "passive"))
    )
    (net (code "29") (name "Net-(D3-K)") (class "Default")
      (node (ref "D3") (pin "2") (pinfunction "K_2") (pintype "passive"))
      (node (ref "L4") (pin "1") (pinfunction "1_1") (pintype "passive"))
      (node (ref "U20") (pin "6") (pinfunction "+Vout_6") (pintype "passive"))
    )
    (net (code "30") (name "Net-(D4-A)") (class "Default")
      (node (ref "D4") (pin "1") (pinfunction "A_1") (pintype "passive"))
      (node (ref "L5") (pin "1") (pinfunction "1_1") (pintype "passive"))
      (node (ref "U20") (pin "4") (pinfunction "-Vout_4") (pintype "passive"))
    )
    (net (code "31") (name "Net-(D5-A)") (class "Default")
      (node (ref "D5") (pin "1") (pinfunction "A_1") (pintype "passive"))
      (node (ref "P16") (pin "2") (pinfunction "2_2") (pintype "passive"))
      (node (ref "P17") (pin "2") (pinfunction "2_2") (pintype "passive"))
      (node (ref "Q1") (pin "3") (pinfunction "C_3") (pintype "passive"))
    )
    (net (code "32") (name "Net-(F1-Pad1)") (class "Default")
      (node (ref "F1") (pin "1") (pintype "power_in"))
      (node (ref "P11") (pin "1") (pinfunction "1_1") (pintype "passive"))
      (node (ref "P9") (pin "1") (pinfunction "1_1") (pintype "passive"))
      (node (ref "R33") (pin "2") (pinfunction "2_2") (pintype "passive"))
    )
    (net (code "33") (name "Net-(LED6-PadK)") (class "Default")
      (node (ref "LED6") (pin "K") (pinfunction "K_K") (pintype "passive"))
      (node (ref "R51") (pin "2") (pinfunction "2_2") (pintype "passive"))
    )
    (net (code "34") (name "Net-(LED7-PadA)") (class "Default")
      (node (ref "LED7") (pin "A") (pinfunction "A_A") (pintype "passive"))
      (node (ref "R47") (pin "1") (pinfunction "1_1") (pintype "passive"))
    )
    (net (code "35") (name "Net-(LED8-PadA)") (class "Default")
      (node (ref "LED8") (pin "A") (pinfunction "A_A") (pintype "passive"))
      (node (ref "R48") (pin "1") (pinfunction "1_1") (pintype "passive"))
    )
    (net (code "36") (name "Net-(LED9-PadA)") (class "Default")
      (node (ref "LED9") (pin "A") (pinfunction "A_A") (pintype "passive"))
      (node (ref "R49") (pin "1") (pinfunction "1_1") (pintype "passive"))
    )
    (net (code "37") (name "Net-(LED10-PadA)") (class "Default")
      (node (ref "LED10") (pin "A") (pinfunction "A_A") (pintype "passive"))
      (node (ref "R33") (pin "1") (pinfunction "1_1") (pintype "passive"))
    )
    (net (code "38") (name "Net-(LED11-PadA)") (class "Default")
      (node (ref "LED11") (pin "A") (pinfunction "A_A") (pintype "passive"))
      (node (ref "R70") (pin "1") (pinfunction "1_1") (pintype "passive"))
    )
    (net (code "39") (name "Net-(LED12-PadA)") (class "Default")
      (node (ref "LED12") (pin "A") (pinfunction "A_A") (pintype "passive"))
      (node (ref "R72") (pin "1") (pinfunction "1_1") (pintype "passive"))
    )
    (net (code "40") (name "Net-(Q1-B)") (class "Default")
      (node (ref "Q1") (pin "1") (pinfunction "B_1") (pintype "passive"))
      (node (ref "R73") (pin "2") (pinfunction "2_2") (pintype "passive"))
    )
    (net (code "41") (name "Net-(U11-Vout)") (class "Default")
      (node (ref "R41") (pin "1") (pinfunction "1_1") (pintype "passive"))
      (node (ref "U11") (pin "3") (pinfunction "Vout_3") (pintype "passive"))
      (node (ref "U13") (pin "4") (pinfunction "Vsense+_4") (pintype "input"))
    )
    (net (code "42") (name "Net-(U14-Vout)") (class "Default")
      (node (ref "R46") (pin "1") (pinfunction "1_1") (pintype "passive"))
      (node (ref "U14") (pin "3") (pinfunction "Vout_3") (pintype "passive"))
      (node (ref "U15") (pin "4") (pinfunction "Vsense+_4") (pintype "input"))
    )
    (net (code "43") (name "Net-(U16-Vout)") (class "Default")
      (node (ref "R53") (pin "1") (pinfunction "1_1") (pintype "passive"))
      (node (ref "U16") (pin "3") (pinfunction "Vout_3") (pintype "passive"))
      (node (ref "U17") (pin "4") (pinfunction "Vsense+_4") (pintype "input"))
    )
    (net (code "44") (name "Net-(U19-RB4)") (class "Default")
      (node (ref "R70") (pin "2") (pinfunction "2_2") (pintype "passive"))
      (node (ref "U19") (pin "25") (pinfunction "RB4_25") (pintype "bidirectional"))
    )
    (net (code "45") (name "unconnected-(J3-Pad6)") (class "Default")
      (node (ref "J3") (pin "6") (pinfunction "6_6") (pintype "passive"))
    )
    (net (code "46") (name "unconnected-(P20-Pad2)") (class "Default")
      (node (ref "P20") (pin "2") (pinfunction "2_2") (pintype "passive"))
    )
    (net (code "47") (name "unconnected-(P20-Pad3)") (class "Default")
      (node (ref "P20") (pin "3") (pinfunction "3_3") (pintype "passive"))
    )
    (net (code "48") (name "unconnected-(P20-Pad6)") (class "Default")
      (node (ref "P20") (pin "6") (pinfunction "6_6") (pintype "passive"))
    )
    (net (code "49") (name "unconnected-(U19-RA4-Pad6)") (class "Default")
      (node (ref "U19") (pin "6") (pinfunction "RA4_6") (pintype "bidirectional"))
    )
    (net (code "50") (name "unconnected-(U19-RA6-Pad10)") (class "Default")
      (node (ref "U19") (pin "10") (pinfunction "RA6_10") (pintype "bidirectional"))
    )
    (net (code "51") (name "unconnected-(U19-RA7-Pad9)") (class "Default")
      (node (ref "U19") (pin "9") (pinfunction "RA7_9") (pintype "bidirectional"))
    )
    (net (code "52") (name "unconnected-(U19-RB2-Pad23)") (class "Default")
      (node (ref "U19") (pin "23") (pinfunction "RB2_23") (pintype "bidirectional"))
    )
    (net (code "53") (name "unconnected-(U19-RB3-Pad24)") (class "Default")
      (node (ref "U19") (pin "24") (pinfunction "RB3_24") (pintype "bidirectional"))
    )
    (net (code "54") (name "unconnected-(U19-RB5-Pad26)") (class "Default")
      (node (ref "U19") (pin "26") (pinfunction "RB5_26") (pintype "bidirectional"))
    )
    (net (code "55") (name "unconnected-(U19-RC0-Pad11)") (class "Default")
      (node (ref "U19") (pin "11") (pinfunction "RC0_11") (pintype "bidirectional"))
    )
  )
)
